# logger2.net
KiCad netlist of a schematic drawn in EAGLE
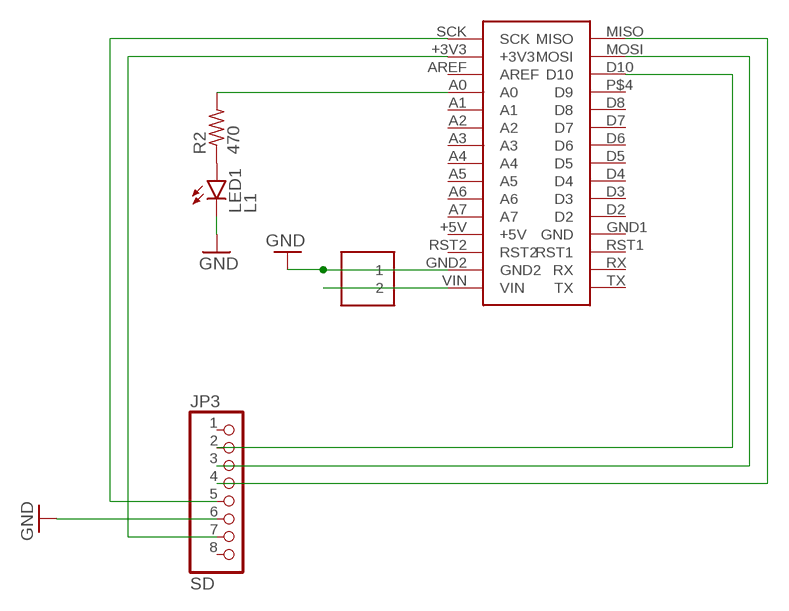
[diagram p0: schematic, sheet 1]

(export (version "E")
  (design (tool "Eeschema 10.0.6"))
  (components
    (comp (ref "J1")
      (value "1X2-3.5MM")
      (footprint "eagle-import:1X2-3.5MM")
      (libsource (lib "eagle-import") (part "1X2-3.5MM"))
    )
    (comp (ref "JP3")
      (value "SD")
      (footprint "eagle-import:1X08-BIG")
      (libsource (lib "eagle-import") (part "PINHD-1X8BIG"))
    )
    (comp (ref "LED1")
      (value "L1")
      (footprint "eagle-import:SFH482")
      (libsource (lib "eagle-import") (part "LEDSFH482"))
    )
    (comp (ref "MC1")
      (value "NANODEVICE")
      (footprint "eagle-import:NANO")
      (libsource (lib "eagle-import") (part "NANODEVICE"))
    )
    (comp (ref "R2")
      (value "470")
      (footprint "eagle-import:V526-0")
      (libsource (lib "eagle-import") (part "R-US_V526-0"))
    )
  )
  (nets
    (net (code "1") (name "GND") (class "Default")
      (node (ref "J1") (pin "1") (pinfunction "1_1") (pintype "passive"))
      (node (ref "JP3") (pin "6") (pinfunction "6_6") (pintype "passive"))
      (node (ref "LED1") (pin "K") (pinfunction "C_K") (pintype "passive"))
      (node (ref "MC1") (pin "GND2") (pinfunction "GND2_GND2") (pintype "bidirectional"))
    )
    (net (code "2") (name "Net-(J1-Pad2)") (class "Default")
      (node (ref "J1") (pin "2") (pinfunction "2_2") (pintype "passive"))
      (node (ref "MC1") (pin "VIN") (pinfunction "VIN_VIN") (pintype "bidirectional"))
    )
    (net (code "3") (name "Net-(JP3-Pad2)") (class "Default")
      (node (ref "JP3") (pin "2") (pinfunction "2_2") (pintype "passive"))
      (node (ref "MC1") (pin "D10") (pinfunction "D10_D10") (pintype "bidirectional"))
    )
    (net (code "4") (name "Net-(JP3-Pad3)") (class "Default")
      (node (ref "JP3") (pin "3") (pinfunction "3_3") (pintype "passive"))
      (node (ref "MC1") (pin "MOSI") (pinfunction "MOSI_MOSI") (pintype "bidirectional"))
    )
    (net (code "5") (name "Net-(JP3-Pad4)") (class "Default")
      (node (ref "JP3") (pin "4") (pinfunction "4_4") (pintype "passive"))
      (node (ref "MC1") (pin "MISO") (pinfunction "MISO_MISO") (pintype "bidirectional"))
    )
    (net (code "6") (name "Net-(JP3-Pad5)") (class "Default")
      (node (ref "JP3") (pin "5") (pinfunction "5_5") (pintype "passive"))
      (node (ref "MC1") (pin "SCK") (pinfunction "SCK_SCK") (pintype "bidirectional"))
    )
    (net (code "7") (name "Net-(JP3-Pad7)") (class "Default")
      (node (ref "JP3") (pin "7") (pinfunction "7_7") (pintype "passive"))
      (node (ref "MC1") (pin "+3V3") (pinfunction "+3V3_+3V3") (pintype "bidirectional"))
    )
    (net (code "8") (name "Net-(LED1-PadA)") (class "Default")
      (node (ref "LED1") (pin "A") (pinfunction "A_A") (pintype "passive"))
      (node (ref "R2") (pin "1") (pinfunction "1_1") (pintype "passive"))
    )
    (net (code "9") (name "Net-(MC1-PadA0)") (class "Default")
      (node (ref "MC1") (pin "A0") (pinfunction "A0_A0") (pintype "bidirectional"))
      (node (ref "R2") (pin "2") (pinfunction "2_2") (pintype "passive"))
    )
    (net (code "10") (name "unconnected-(JP3-Pad1)") (class "Default")
      (node (ref "JP3") (pin "1") (pinfunction "1_1") (pintype "passive"))
    )
    (net (code "11") (name "unconnected-(JP3-Pad8)") (class "Default")
      (node (ref "JP3") (pin "8") (pinfunction "8_8") (pintype "passive"))
    )
    (net (code "12") (name "unconnected-(MC1-D9-PadP$4)") (class "Default")
      (node (ref "MC1") (pin "P$4") (pinfunction "D9_P$4") (pintype "bidirectional"))
    )
    (net (code "13") (name "unconnected-(MC1-GND-PadGND1)") (class "Default")
      (node (ref "MC1") (pin "GND1") (pinfunction "GND_GND1") (pintype "bidirectional"))
    )
    (net (code "14") (name "unconnected-(MC1-Pad+5V)") (class "Default")
      (node (ref "MC1") (pin "+5V") (pinfunction "+5V_+5V") (pintype "bidirectional"))
    )
    (net (code "15") (name "unconnected-(MC1-PadA1)") (class "Default")
      (node (ref "MC1") (pin "A1") (pinfunction "A1_A1") (pintype "bidirectional"))
    )
    (net (code "16") (name "unconnected-(MC1-PadA2)") (class "Default")
      (node (ref "MC1") (pin "A2") (pinfunction "A2_A2") (pintype "bidirectional"))
    )
    (net (code "17") (name "unconnected-(MC1-PadA3)") (class "Default")
      (node (ref "MC1") (pin "A3") (pinfunction "A3_A3") (pintype "bidirectional"))
    )
    (net (code "18") (name "unconnected-(MC1-PadA4)") (class "Default")
      (node (ref "MC1") (pin "A4") (pinfunction "A4_A4") (pintype "bidirectional"))
    )
    (net (code "19") (name "unconnected-(MC1-PadA5)") (class "Default")
      (node (ref "MC1") (pin "A5") (pinfunction "A5_A5") (pintype "bidirectional"))
    )
    (net (code "20") (name "unconnected-(MC1-PadA6)") (class "Default")
      (node (ref "MC1") (pin "A6") (pinfunction "A6_A6") (pintype "bidirectional"))
    )
    (net (code "21") (name "unconnected-(MC1-PadA7)") (class "Default")
      (node (ref "MC1") (pin "A7") (pinfunction "A7_A7") (pintype "bidirectional"))
    )
    (net (code "22") (name "unconnected-(MC1-PadAREF)") (class "Default")
      (node (ref "MC1") (pin "AREF") (pinfunction "AREF_AREF") (pintype "bidirectional"))
    )
    (net (code "23") (name "unconnected-(MC1-PadD2)") (class "Default")
      (node (ref "MC1") (pin "D2") (pinfunction "D2_D2") (pintype "bidirectional"))
    )
    (net (code "24") (name "unconnected-(MC1-PadD3)") (class "Default")
      (node (ref "MC1") (pin "D3") (pinfunction "D3_D3") (pintype "bidirectional"))
    )
    (net (code "25") (name "unconnected-(MC1-PadD4)") (class "Default")
      (node (ref "MC1") (pin "D4") (pinfunction "D4_D4") (pintype "bidirectional"))
    )
    (net (code "26") (name "unconnected-(MC1-PadD5)") (class "Default")
      (node (ref "MC1") (pin "D5") (pinfunction "D5_D5") (pintype "bidirectional"))
    )
    (net (code "27") (name "unconnected-(MC1-PadD6)") (class "Default")
      (node (ref "MC1") (pin "D6") (pinfunction "D6_D6") (pintype "bidirectional"))
    )
    (net (code "28") (name "unconnected-(MC1-PadD7)") (class "Default")
      (node (ref "MC1") (pin "D7") (pinfunction "D7_D7") (pintype "bidirectional"))
    )
    (net (code "29") (name "unconnected-(MC1-PadD8)") (class "Default")
      (node (ref "MC1") (pin "D8") (pinfunction "D8_D8") (pintype "bidirectional"))
    )
    (net (code "30") (name "unconnected-(MC1-PadRST1)") (class "Default")
      (node (ref "MC1") (pin "RST1") (pinfunction "RST1_RST1") (pintype "bidirectional"))
    )
    (net (code "31") (name "unconnected-(MC1-PadRST2)") (class "Default")
      (node (ref "MC1") (pin "RST2") (pinfunction "RST2_RST2") (pintype "bidirectional"))
    )
    (net (code "32") (name "unconnected-(MC1-PadRX)") (class "Default")
      (node (ref "MC1") (pin "RX") (pinfunction "RX_RX") (pintype "bidirectional"))
    )
    (net (code "33") (name "unconnected-(MC1-PadTX)") (class "Default")
      (node (ref "MC1") (pin "TX") (pinfunction "TX_TX") (pintype "bidirectional"))
    )
  )
)
